# main.net
KiCad netlist of a schematic drawn in EAGLE
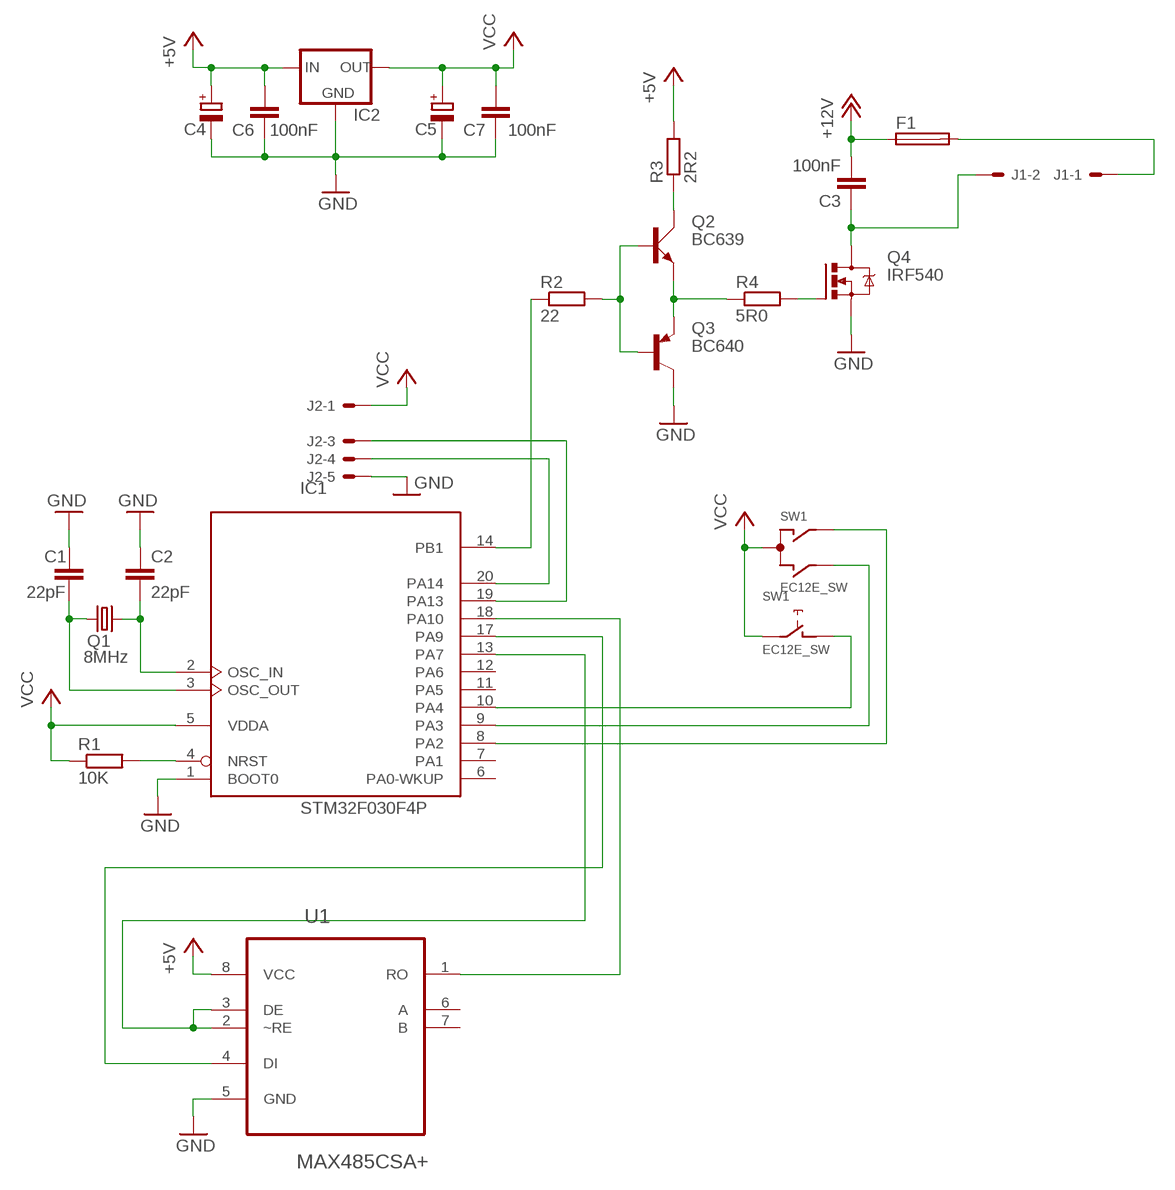
[diagram p0: schematic, sheet 1]

(export (version "E")
  (design (tool "Eeschema 10.0.6"))
  (components
    (comp (ref "C1")
      (value "22pF")
      (footprint "eagle-import:C2.5-3")
      (libsource (lib "eagle-import") (part "C2,5-3"))
    )
    (comp (ref "C2")
      (value "22pF")
      (footprint "eagle-import:C2.5-3")
      (libsource (lib "eagle-import") (part "C2,5-3"))
    )
    (comp (ref "C3")
      (value "100nF")
      (footprint "eagle-import:C2.5-3")
      (libsource (lib "eagle-import") (part "C2,5-3"))
    )
    (comp (ref "C4")
      (value "CPOL-EU085CS-1AR")
      (footprint "eagle-import:085CS_1AR")
      (libsource (lib "eagle-import") (part "CPOL-EU085CS-1AR"))
    )
    (comp (ref "C5")
      (value "CPOL-EU085CS-1AR")
      (footprint "eagle-import:085CS_1AR")
      (libsource (lib "eagle-import") (part "CPOL-EU085CS-1AR"))
    )
    (comp (ref "C6")
      (value "100nF")
      (footprint "eagle-import:C2.5-3")
      (libsource (lib "eagle-import") (part "C2,5-3"))
    )
    (comp (ref "C7")
      (value "100nF")
      (footprint "eagle-import:C2.5-3")
      (libsource (lib "eagle-import") (part "C2,5-3"))
    )
    (comp (ref "F1")
      (value "TR5")
      (footprint "eagle-import:TR5")
      (libsource (lib "eagle-import") (part "TR5"))
    )
    (comp (ref "IC1")
      (value "STM32F030F4P")
      (footprint "eagle-import:TSSOP20-I")
      (libsource (lib "eagle-import") (part "STM32F030FP4"))
    )
    (comp (ref "IC2")
      (value "78LXX")
      (footprint "eagle-import:78LXX")
      (libsource (lib "eagle-import") (part "78LXX"))
    )
    (comp (ref "J1")
      (value "22-05-7028-02")
      (footprint "eagle-import:7395-02")
      (libsource (lib "eagle-import") (part "22-?-0205-7028"))
    )
    (comp (ref "J2")
      (value "22-27-2051-05")
      (footprint "eagle-import:6410-05")
      (libsource (lib "eagle-import") (part "22-?-0527-2051"))
    )
    (comp (ref "Q1")
      (value "8MHz")
      (footprint "eagle-import:HC18U-V")
      (libsource (lib "eagle-import") (part "CRYSTALHC18U-V"))
    )
    (comp (ref "Q2")
      (value "BC639")
      (footprint "eagle-import:SOT54D")
      (libsource (lib "eagle-import") (part "BC639"))
    )
    (comp (ref "Q3")
      (value "BC640")
      (footprint "eagle-import:TO92-BCE")
      (libsource (lib "eagle-import") (part "BC640"))
    )
    (comp (ref "Q4")
      (value "IRF540")
      (footprint "eagle-import:TO220BV")
      (libsource (lib "eagle-import") (part "IRF540"))
    )
    (comp (ref "R1")
      (value "10K")
      (footprint "eagle-import:R1206")
      (libsource (lib "eagle-import") (part "R-EU_R1206"))
    )
    (comp (ref "R2")
      (value "22")
      (footprint "eagle-import:R1206")
      (libsource (lib "eagle-import") (part "R-EU_R1206"))
    )
    (comp (ref "R3")
      (value "2R2")
      (footprint "eagle-import:R1206")
      (libsource (lib "eagle-import") (part "R-EU_R1206"))
    )
    (comp (ref "R4")
      (value "5R0")
      (footprint "eagle-import:R1206")
      (libsource (lib "eagle-import") (part "R-EU_R1206"))
    )
    (comp (ref "SW1")
      (value "EC12E_SW")
      (footprint "eagle-import:ALPS_EC12E_SW")
      (fields (field (name "MPN") "EC12E2424407"))
      (libsource (lib "eagle-import") (part "EC12E_SW"))
    )
    (comp (ref "U1")
      (value "MAX485CSA+")
      (footprint "eagle-import:SOIC127P600X175-8N")
      (libsource (lib "eagle-import") (part "MAX485CSA+"))
    )
  )
  (nets
    (net (code "1") (name "+5V") (class "Default")
      (node (ref "C4") (pin "+") (pinfunction "+_+") (pintype "passive"))
      (node (ref "C6") (pin "2") (pinfunction "2_2") (pintype "passive"))
      (node (ref "IC2") (pin "IN") (pinfunction "IN_IN") (pintype "input"))
      (node (ref "R3") (pin "2") (pinfunction "2_2") (pintype "passive"))
      (node (ref "U1") (pin "8") (pinfunction "VCC_8") (pintype "power_in"))
    )
    (net (code "2") (name "+12V") (class "Default")
      (node (ref "C3") (pin "2") (pinfunction "2_2") (pintype "passive"))
      (node (ref "F1") (pin "1") (pinfunction "1_1") (pintype "passive"))
    )
    (net (code "3") (name "GND") (class "Default")
      (node (ref "C1") (pin "1") (pinfunction "1_1") (pintype "passive"))
      (node (ref "C2") (pin "1") (pinfunction "1_1") (pintype "passive"))
      (node (ref "C4") (pin "-") (pinfunction "-_-") (pintype "passive"))
      (node (ref "C5") (pin "-") (pinfunction "-_-") (pintype "passive"))
      (node (ref "C6") (pin "1") (pinfunction "1_1") (pintype "passive"))
      (node (ref "C7") (pin "1") (pinfunction "1_1") (pintype "passive"))
      (node (ref "IC1") (pin "1") (pinfunction "BOOT0_1") (pintype "input"))
      (node (ref "IC2") (pin "GND") (pinfunction "GND_GND") (pintype "input"))
      (node (ref "J2") (pin "5") (pinfunction "S_5") (pintype "passive"))
      (node (ref "Q3") (pin "C") (pinfunction "C_C") (pintype "passive"))
      (node (ref "Q4") (pin "S") (pinfunction "S_S") (pintype "passive"))
      (node (ref "U1") (pin "5") (pinfunction "GND_5") (pintype "passive"))
    )
    (net (code "4") (name "Net-(IC1A-NRST)") (class "Default")
      (node (ref "IC1") (pin "4") (pinfunction "NRST_4") (pintype "bidirectional"))
      (node (ref "R1") (pin "2") (pinfunction "2_2") (pintype "passive"))
    )
    (net (code "5") (name "Net-(IC1A-OSC_IN)") (class "Default")
      (node (ref "C2") (pin "2") (pinfunction "2_2") (pintype "passive"))
      (node (ref "IC1") (pin "2") (pinfunction "OSC_IN_2") (pintype "bidirectional"))
      (node (ref "Q1") (pin "2") (pinfunction "2_2") (pintype "passive"))
    )
    (net (code "6") (name "Net-(IC1A-OSC_OUT)") (class "Default")
      (node (ref "C1") (pin "2") (pinfunction "2_2") (pintype "passive"))
      (node (ref "IC1") (pin "3") (pinfunction "OSC_OUT_3") (pintype "bidirectional"))
      (node (ref "Q1") (pin "1") (pinfunction "1_1") (pintype "passive"))
    )
    (net (code "7") (name "Net-(IC1A-PA2)") (class "Default")
      (node (ref "IC1") (pin "8") (pinfunction "PA2_8") (pintype "bidirectional"))
      (node (ref "SW1") (pin "A") (pinfunction "A_A") (pintype "passive"))
    )
    (net (code "8") (name "Net-(IC1A-PA3)") (class "Default")
      (node (ref "IC1") (pin "9") (pinfunction "PA3_9") (pintype "bidirectional"))
      (node (ref "SW1") (pin "B") (pinfunction "B_B") (pintype "passive"))
    )
    (net (code "9") (name "Net-(IC1A-PA4)") (class "Default")
      (node (ref "IC1") (pin "10") (pinfunction "PA4_10") (pintype "bidirectional"))
      (node (ref "SW1") (pin "D") (pinfunction "1_D") (pintype "passive"))
    )
    (net (code "10") (name "Net-(IC1A-PA7)") (class "Default")
      (node (ref "IC1") (pin "13") (pinfunction "PA7_13") (pintype "bidirectional"))
      (node (ref "U1") (pin "2") (pinfunction "~{RE}_2") (pintype "input"))
      (node (ref "U1") (pin "3") (pinfunction "DE_3") (pintype "input"))
    )
    (net (code "11") (name "Net-(IC1A-PA9)") (class "Default")
      (node (ref "IC1") (pin "17") (pinfunction "PA9_17") (pintype "bidirectional"))
      (node (ref "U1") (pin "4") (pinfunction "DI_4") (pintype "input"))
    )
    (net (code "12") (name "Net-(IC1A-PA10)") (class "Default")
      (node (ref "IC1") (pin "18") (pinfunction "PA10_18") (pintype "bidirectional"))
      (node (ref "U1") (pin "1") (pinfunction "RO_1") (pintype "output"))
    )
    (net (code "13") (name "Net-(IC1A-PA13)") (class "Default")
      (node (ref "IC1") (pin "19") (pinfunction "PA13_19") (pintype "bidirectional"))
      (node (ref "J2") (pin "3") (pinfunction "S_3") (pintype "passive"))
    )
    (net (code "14") (name "Net-(IC1A-PA14)") (class "Default")
      (node (ref "IC1") (pin "20") (pinfunction "PA14_20") (pintype "bidirectional"))
      (node (ref "J2") (pin "4") (pinfunction "S_4") (pintype "passive"))
    )
    (net (code "15") (name "Net-(IC1A-PB1)") (class "Default")
      (node (ref "IC1") (pin "14") (pinfunction "PB1_14") (pintype "bidirectional"))
      (node (ref "R2") (pin "1") (pinfunction "1_1") (pintype "passive"))
    )
    (net (code "16") (name "Net-(J1A-S)") (class "Default")
      (node (ref "F1") (pin "2") (pinfunction "2_2") (pintype "passive"))
      (node (ref "J1") (pin "1") (pinfunction "S_1") (pintype "passive"))
    )
    (net (code "17") (name "Net-(J1B-S)") (class "Default")
      (node (ref "C3") (pin "1") (pinfunction "1_1") (pintype "passive"))
      (node (ref "J1") (pin "2") (pinfunction "S_2") (pintype "passive"))
      (node (ref "Q4") (pin "D") (pinfunction "D_D") (pintype "passive"))
    )
    (net (code "18") (name "Net-(Q2-PadB)") (class "Default")
      (node (ref "Q2") (pin "B") (pinfunction "B_B") (pintype "passive"))
      (node (ref "Q3") (pin "B") (pinfunction "B_B") (pintype "passive"))
      (node (ref "R2") (pin "2") (pinfunction "2_2") (pintype "passive"))
    )
    (net (code "19") (name "Net-(Q2-PadC)") (class "Default")
      (node (ref "Q2") (pin "C") (pinfunction "C_C") (pintype "passive"))
      (node (ref "R3") (pin "1") (pinfunction "1_1") (pintype "passive"))
    )
    (net (code "20") (name "Net-(Q2-PadE)") (class "Default")
      (node (ref "Q2") (pin "E") (pinfunction "E_E") (pintype "passive"))
      (node (ref "Q3") (pin "E") (pinfunction "E_E") (pintype "passive"))
      (node (ref "R4") (pin "1") (pinfunction "1_1") (pintype "passive"))
    )
    (net (code "21") (name "Net-(Q4-PadG)") (class "Default")
      (node (ref "Q4") (pin "G") (pinfunction "G_G") (pintype "passive"))
      (node (ref "R4") (pin "2") (pinfunction "2_2") (pintype "passive"))
    )
    (net (code "22") (name "VCC") (class "Default")
      (node (ref "C5") (pin "+") (pinfunction "+_+") (pintype "passive"))
      (node (ref "C7") (pin "2") (pinfunction "2_2") (pintype "passive"))
      (node (ref "IC1") (pin "5") (pinfunction "VDDA_5") (pintype "power_in"))
      (node (ref "IC2") (pin "OUT") (pinfunction "OUT_OUT") (pintype "passive"))
      (node (ref "J2") (pin "1") (pinfunction "S_1") (pintype "passive"))
      (node (ref "R1") (pin "1") (pinfunction "1_1") (pintype "passive"))
      (node (ref "SW1") (pin "C") (pinfunction "C_C") (pintype "passive"))
      (node (ref "SW1") (pin "E") (pinfunction "2_E") (pintype "passive"))
    )
    (net (code "23") (name "unconnected-(IC1A-PA0-WKUP-Pad6)") (class "Default")
      (node (ref "IC1") (pin "6") (pinfunction "PA0-WKUP_6") (pintype "bidirectional"))
    )
    (net (code "24") (name "unconnected-(IC1A-PA1-Pad7)") (class "Default")
      (node (ref "IC1") (pin "7") (pinfunction "PA1_7") (pintype "bidirectional"))
    )
    (net (code "25") (name "unconnected-(IC1A-PA5-Pad11)") (class "Default")
      (node (ref "IC1") (pin "11") (pinfunction "PA5_11") (pintype "bidirectional"))
    )
    (net (code "26") (name "unconnected-(IC1A-PA6-Pad12)") (class "Default")
      (node (ref "IC1") (pin "12") (pinfunction "PA6_12") (pintype "bidirectional"))
    )
    (net (code "27") (name "unconnected-(U1-A-Pad6)") (class "Default")
      (node (ref "U1") (pin "6") (pinfunction "A_6") (pintype "bidirectional"))
    )
    (net (code "28") (name "unconnected-(U1-B-Pad7)") (class "Default")
      (node (ref "U1") (pin "7") (pinfunction "B_7") (pintype "bidirectional"))
    )
  )
)
